# main.net
KiCad netlist of a schematic drawn in Altium Designer
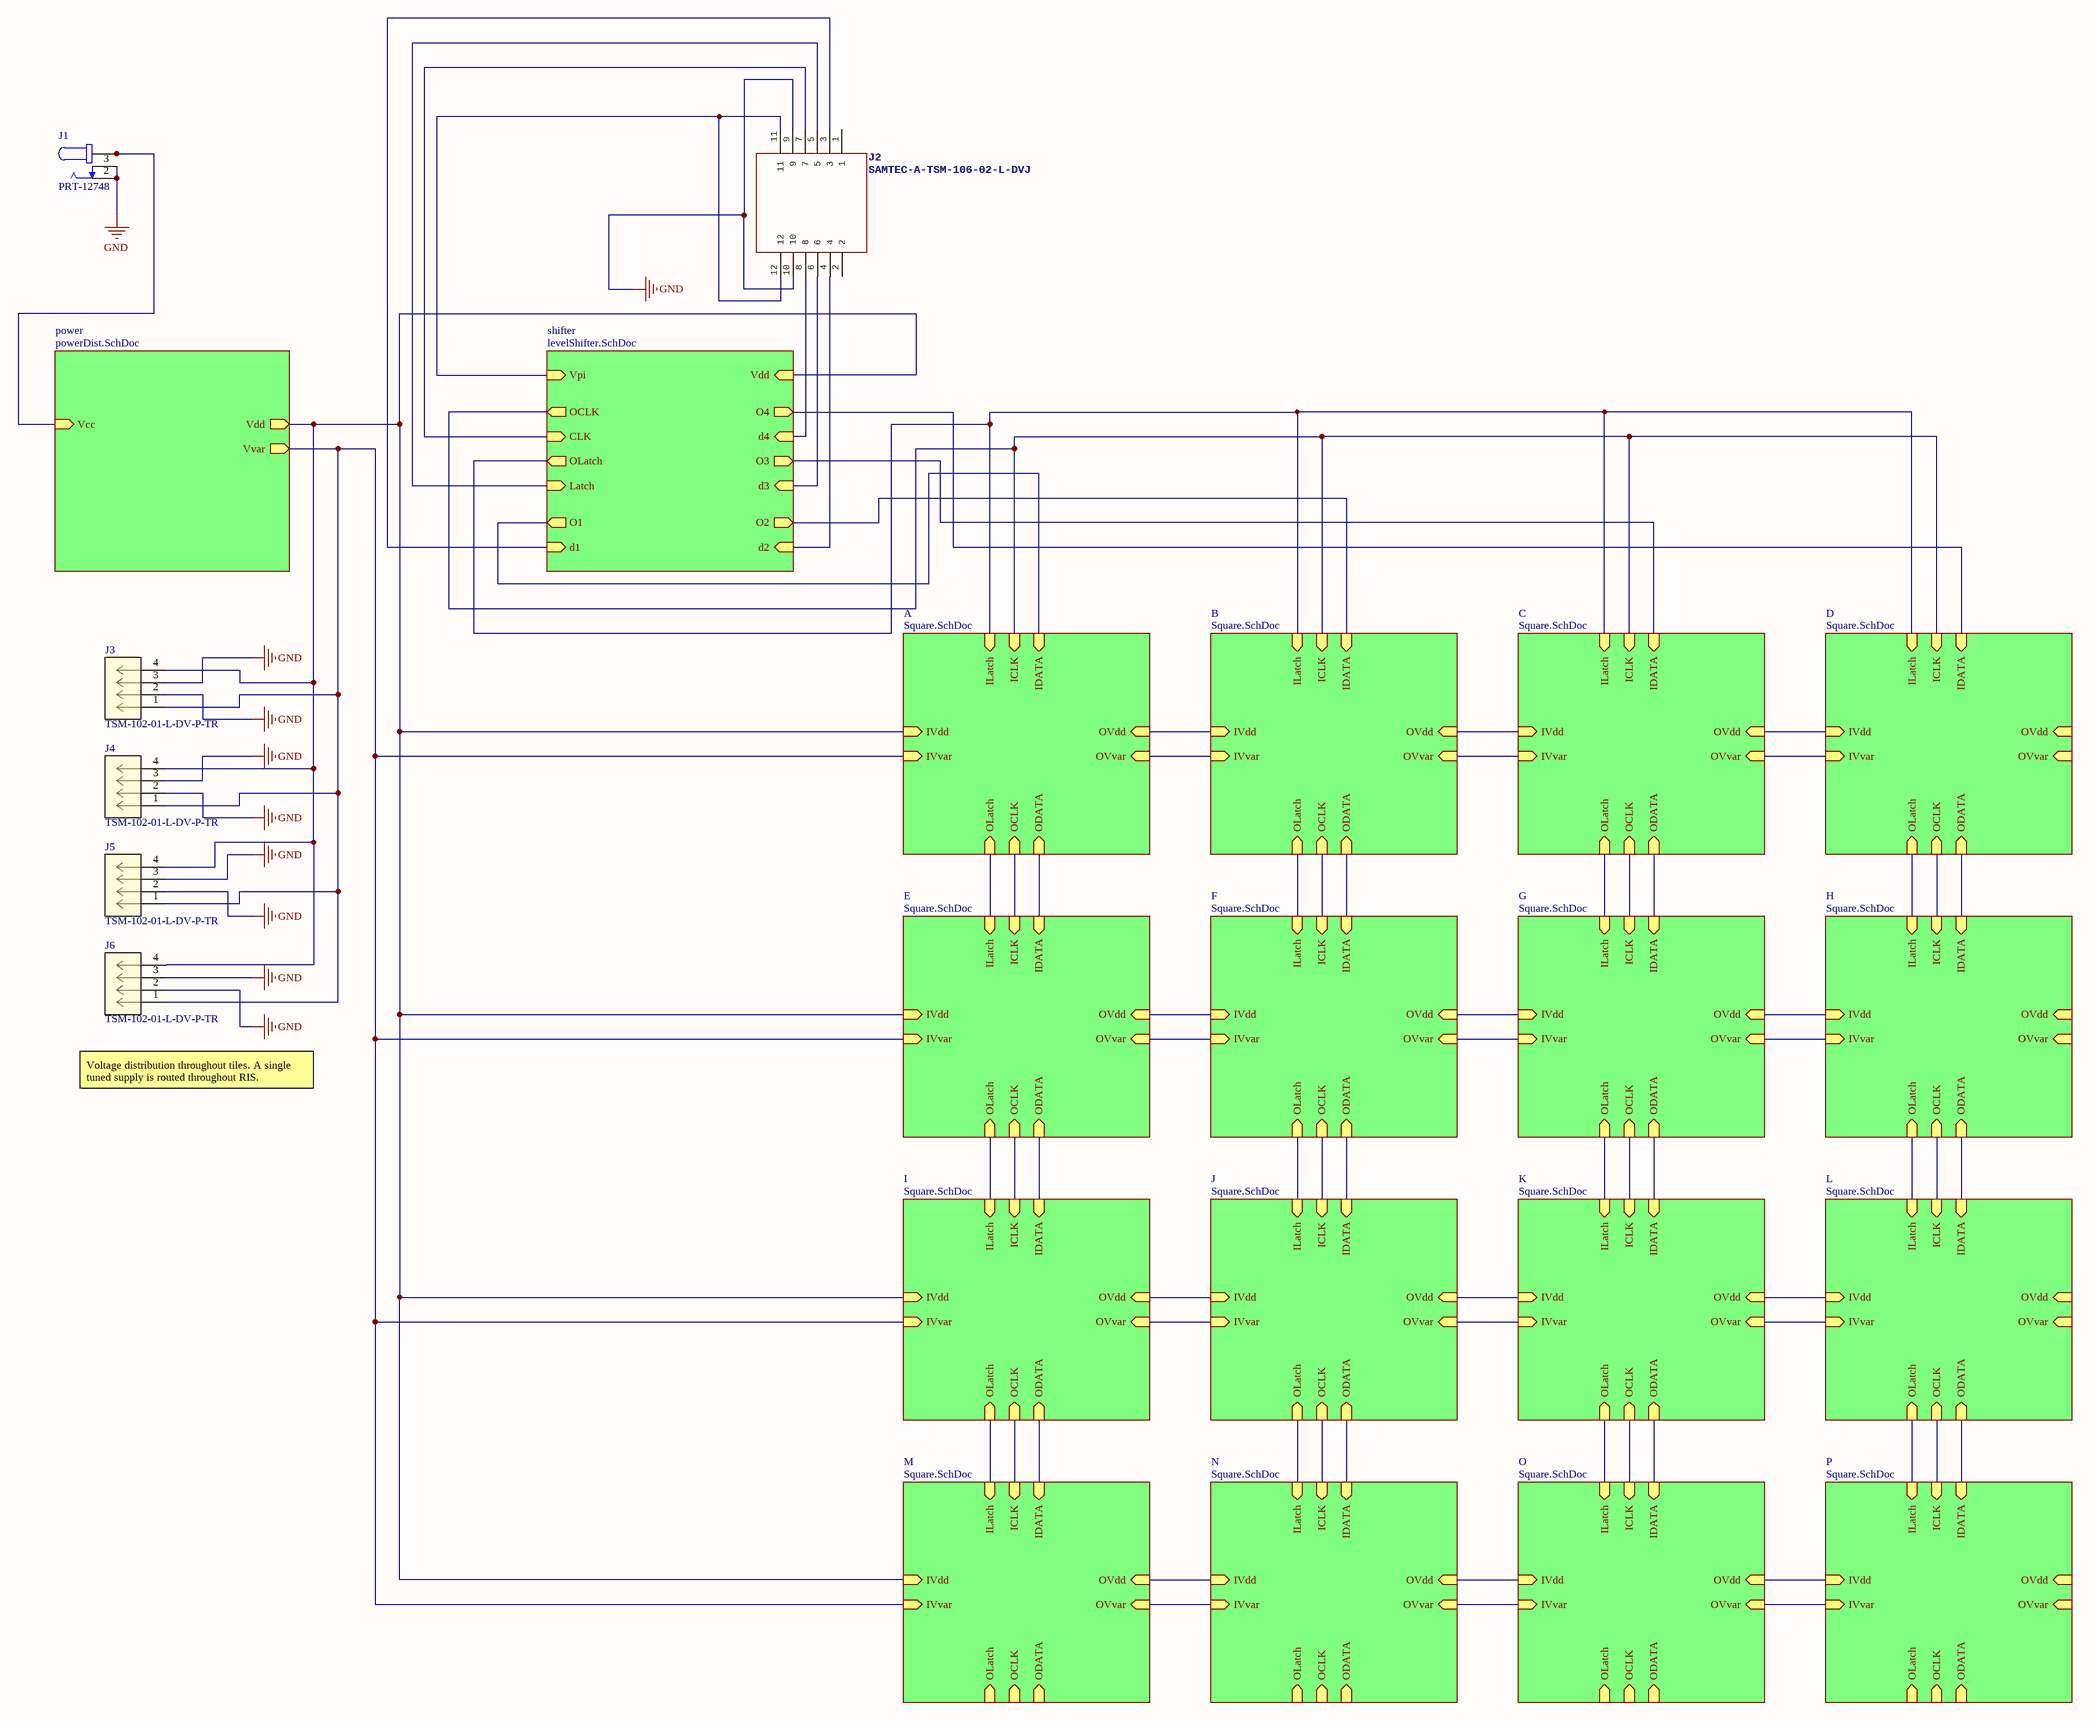
[diagram p0: main.SchDoc]

(export (version "E")
  (design (tool "Eeschema 10.0.6"))
  (components
    (comp (ref "J1")
      (value "PRT-12748")
      (footprint "SPARKFUN_PRT-12748")
      (description "SparkFun Accessories DC Barrel Power Jack Connector SMD")
      (fields (field (name "MF") "SparkFun"))
      (libsource (lib "PRT-12748") (part "PRT-12748"))
    )
    (comp (ref "J2")
      (value "SAMTEC-A-TSM-106-02-L-DVJ")
      (footprint "SAMTEC-A-TSM-106-02-L-DV")
      (libsource (lib "SAMTEC-A-TSM-106-02-L-DV") (part "SAMTEC-A-TSM-106-02-L-DVJ"))
    )
    (comp (ref "J3")
      (value "TSM-102-01-L-DV-P-TR")
      (footprint "SAMTEC-A-TSM-102-02-L-DV")
      (description "No Description Available")
      (fields (field (name "COPYRIGHT") "Copyright (C) 2022 Ultra Librarian. All rights reserved."))
      (libsource (lib "TSM-102-01-L-DV-P-TR") (part "TSM-102-01-L-DV-P-TR"))
    )
    (comp (ref "J4")
      (value "TSM-102-01-L-DV-P-TR")
      (footprint "SAMTEC-A-TSM-102-02-L-DV")
      (description "No Description Available")
      (fields (field (name "COPYRIGHT") "Copyright (C) 2022 Ultra Librarian. All rights reserved."))
      (libsource (lib "TSM-102-01-L-DV-P-TR") (part "TSM-102-01-L-DV-P-TR"))
    )
    (comp (ref "J5")
      (value "TSM-102-01-L-DV-P-TR")
      (footprint "SAMTEC-A-TSM-102-02-L-DV")
      (description "No Description Available")
      (fields (field (name "COPYRIGHT") "Copyright (C) 2022 Ultra Librarian. All rights reserved."))
      (libsource (lib "TSM-102-01-L-DV-P-TR") (part "TSM-102-01-L-DV-P-TR"))
    )
    (comp (ref "J6")
      (value "TSM-102-01-L-DV-P-TR")
      (footprint "SAMTEC-A-TSM-102-02-L-DV")
      (description "No Description Available")
      (fields (field (name "COPYRIGHT") "Copyright (C) 2022 Ultra Librarian. All rights reserved."))
      (libsource (lib "TSM-102-01-L-DV-P-TR") (part "TSM-102-01-L-DV-P-TR"))
    )
  )
  (nets
    (net (code "1") (name "/CLK") (class "Default")
      (node (ref "J2") (pin "7") (pinfunction "7_7") (pintype "passive"))
    )
    (net (code "62") (name "/Latch") (class "Default")
      (node (ref "J2") (pin "5") (pinfunction "5_5") (pintype "passive"))
    )
    (net (code "89") (name "/Vcc") (class "Default")
      (node (ref "J1") (pin "1_1") (pinfunction "1_1_1") (pintype "passive"))
      (node (ref "J1") (pin "1_2") (pinfunction "1_1_2") (pintype "passive"))
    )
    (net (code "90") (name "/Vdd") (class "Default")
      (node (ref "J3") (pin "4") (pinfunction "4_4") (pintype "passive"))
      (node (ref "J4") (pin "4") (pinfunction "4_4") (pintype "passive"))
      (node (ref "J5") (pin "4") (pinfunction "4_4") (pintype "passive"))
      (node (ref "J6") (pin "4") (pinfunction "4_4") (pintype "passive"))
    )
    (net (code "91") (name "/Vpi") (class "Default")
      (node (ref "J2") (pin "11") (pinfunction "11_11") (pintype "passive"))
      (node (ref "J2") (pin "12") (pinfunction "12_12") (pintype "passive"))
    )
    (net (code "92") (name "/Vvar") (class "Default")
      (node (ref "J3") (pin "1") (pinfunction "1_1") (pintype "passive"))
      (node (ref "J4") (pin "1") (pinfunction "1_1") (pintype "passive"))
      (node (ref "J5") (pin "1") (pinfunction "1_1") (pintype "passive"))
      (node (ref "J6") (pin "1") (pinfunction "1_1") (pintype "passive"))
    )
    (net (code "93") (name "/d1") (class "Default")
      (node (ref "J2") (pin "3") (pinfunction "3_3") (pintype "passive"))
    )
    (net (code "94") (name "/d2") (class "Default")
      (node (ref "J2") (pin "4") (pinfunction "4_4") (pintype "passive"))
    )
    (net (code "95") (name "/d3") (class "Default")
      (node (ref "J2") (pin "6") (pinfunction "6_6") (pintype "passive"))
    )
    (net (code "96") (name "/d4") (class "Default")
      (node (ref "J2") (pin "8") (pinfunction "8_8") (pintype "passive"))
    )
    (net (code "97") (name "GND") (class "Default")
      (node (ref "J1") (pin "2") (pinfunction "2_2") (pintype "passive"))
      (node (ref "J1") (pin "3") (pinfunction "3_3") (pintype "passive"))
      (node (ref "J2") (pin "10") (pinfunction "10_10") (pintype "passive"))
      (node (ref "J2") (pin "9") (pinfunction "9_9") (pintype "passive"))
      (node (ref "J3") (pin "2") (pinfunction "2_2") (pintype "passive"))
      (node (ref "J3") (pin "3") (pinfunction "3_3") (pintype "passive"))
      (node (ref "J4") (pin "2") (pinfunction "2_2") (pintype "passive"))
      (node (ref "J4") (pin "3") (pinfunction "3_3") (pintype "passive"))
      (node (ref "J5") (pin "2") (pinfunction "2_2") (pintype "passive"))
      (node (ref "J5") (pin "3") (pinfunction "3_3") (pintype "passive"))
      (node (ref "J6") (pin "2") (pinfunction "2_2") (pintype "passive"))
      (node (ref "J6") (pin "3") (pinfunction "3_3") (pintype "passive"))
    )
    (net (code "98") (name "unconnected-(J2-Pad1)") (class "Default")
      (node (ref "J2") (pin "1") (pinfunction "1_1") (pintype "passive"))
    )
    (net (code "99") (name "unconnected-(J2-Pad2)") (class "Default")
      (node (ref "J2") (pin "2") (pinfunction "2_2") (pintype "passive"))
    )
  )
)
